# mega-sd-easyeda.net
KiCad netlist of a schematic drawn in EasyEDA Pro
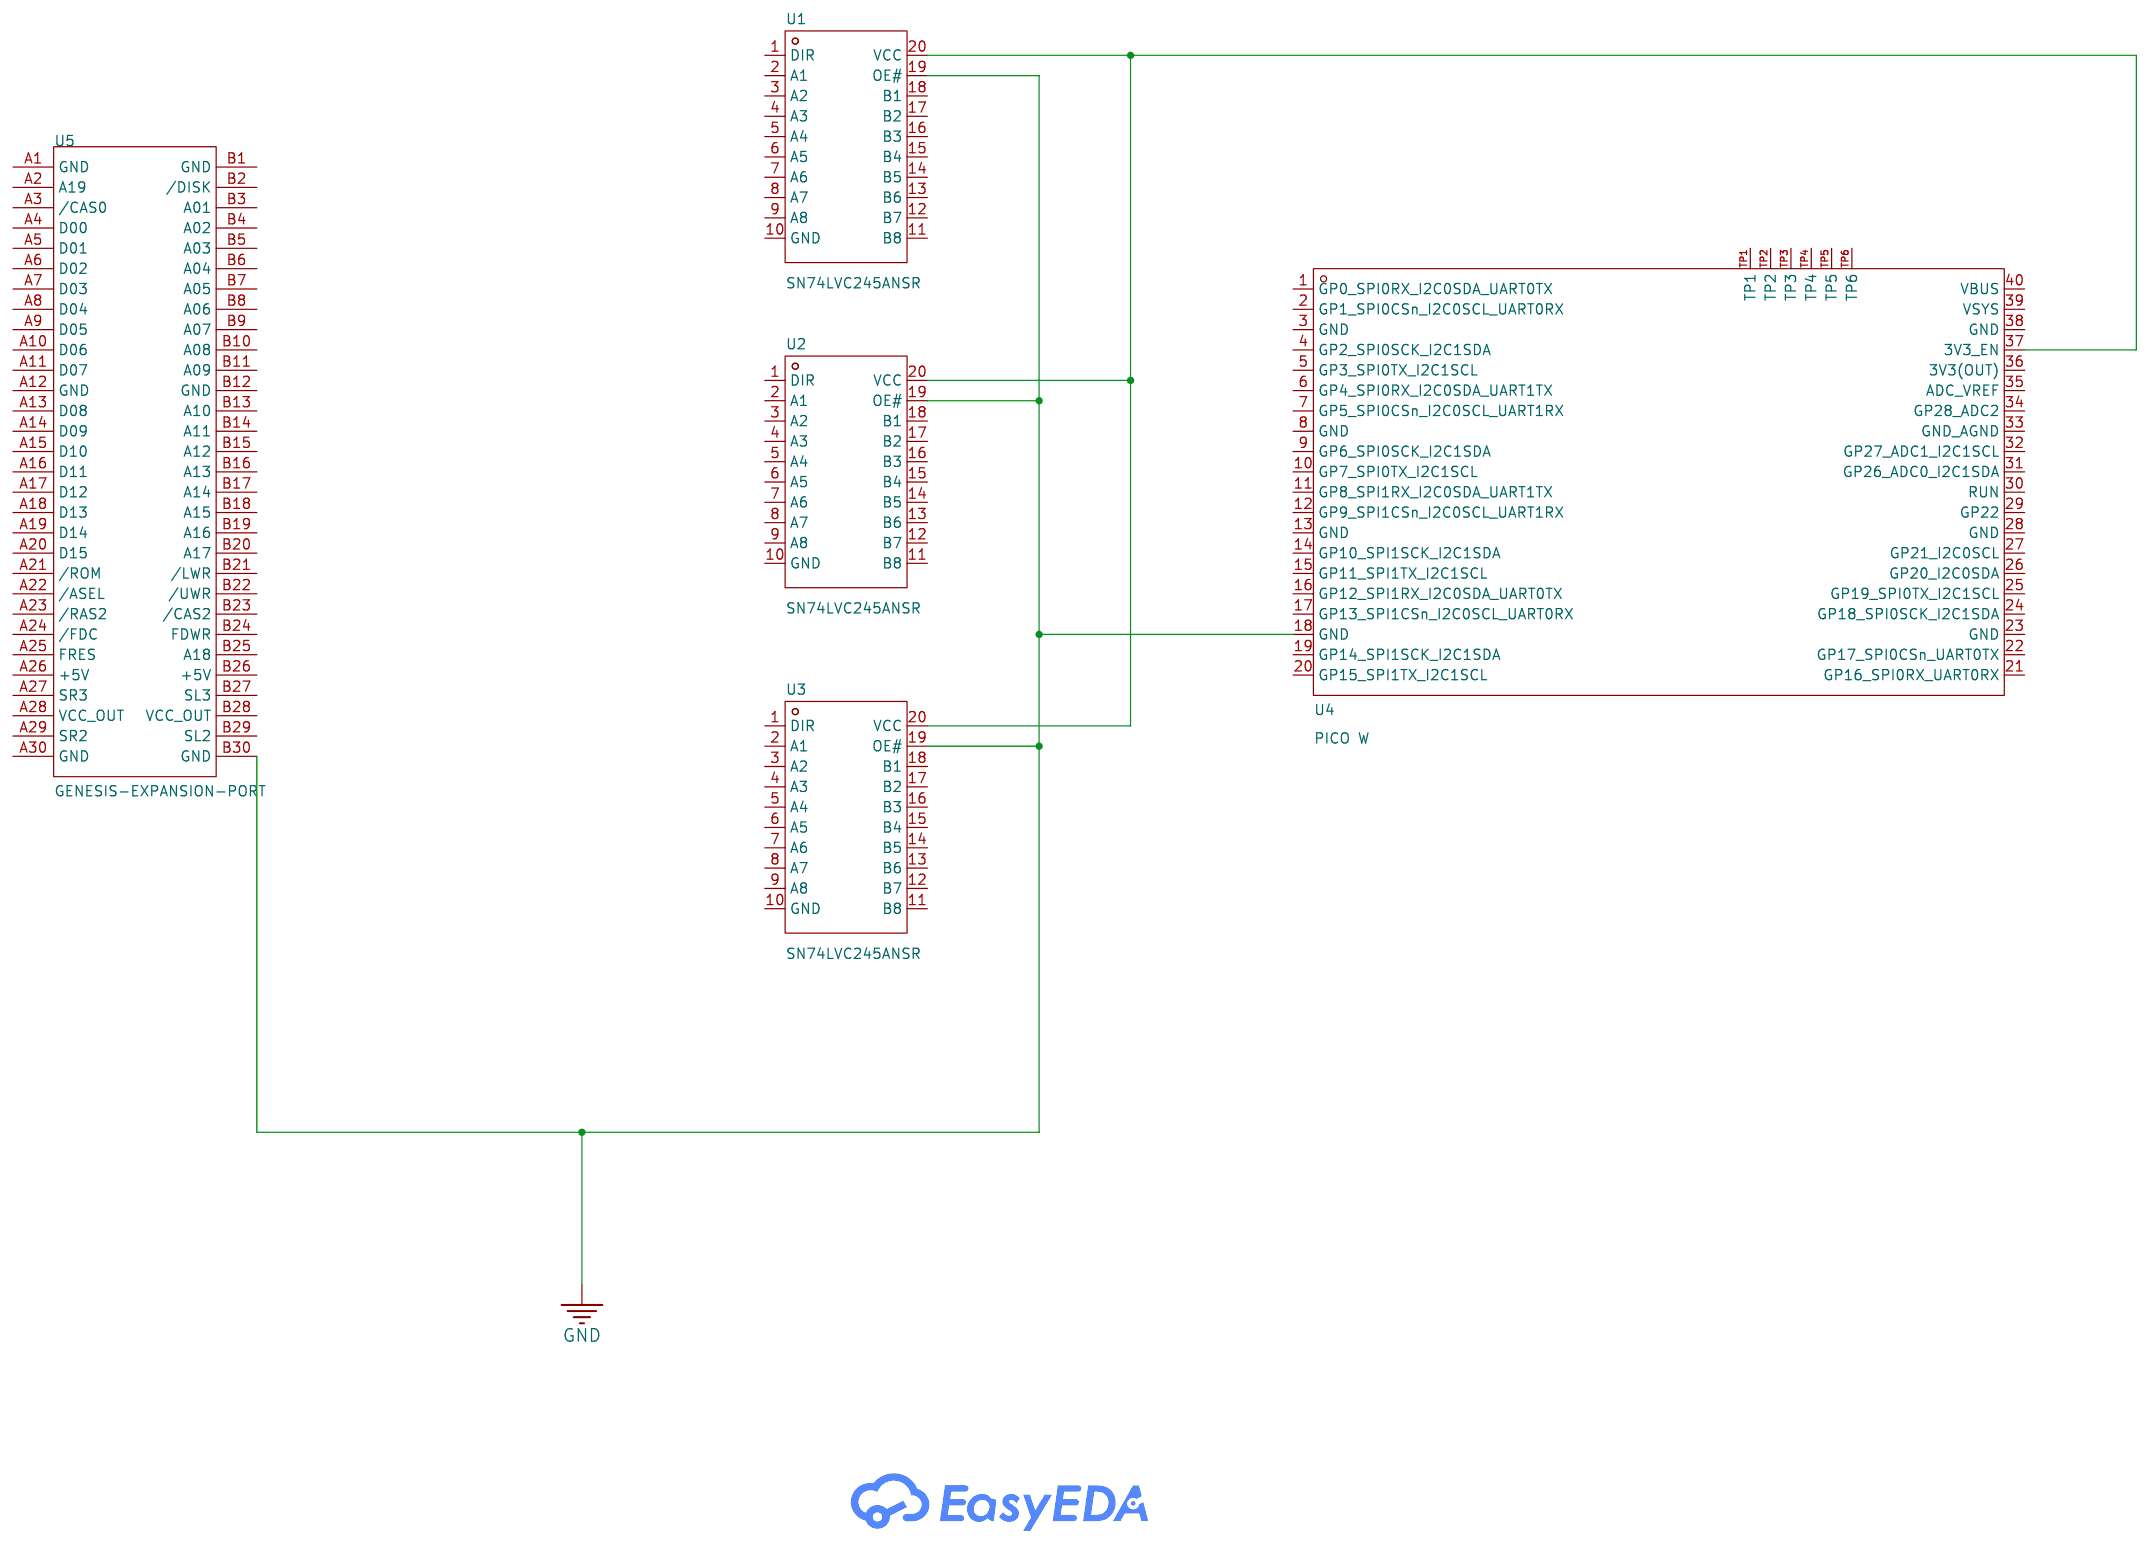
[diagram p0: schematic sheet]

(export (version "E")
  (design (tool "Eeschema 10.0.6"))
  (components
    (comp (ref "U1")
      (value "SN74LVC245ANSR")
      (footprint "easyedapro:SOIC-20_L13.3-W5.5-P1.27-LS7.8-BL")
      (fields (field (name "Manufacturer") "TI(德州仪器)"))
      (libsource (lib "easyedapro") (part "SN74LVC245ANSR"))
    )
    (comp (ref "U2")
      (value "SN74LVC245ANSR")
      (footprint "easyedapro:SOIC-20_L13.3-W5.5-P1.27-LS7.8-BL")
      (fields (field (name "Manufacturer") "TI(德州仪器)"))
      (libsource (lib "easyedapro") (part "SN74LVC245ANSR"))
    )
    (comp (ref "U3")
      (value "SN74LVC245ANSR")
      (footprint "easyedapro:SOIC-20_L13.3-W5.5-P1.27-LS7.8-BL")
      (fields (field (name "Manufacturer") "TI(德州仪器)"))
      (libsource (lib "easyedapro") (part "SN74LVC245ANSR"))
    )
    (comp (ref "U4")
      (value "PICO W")
      (footprint "easyedapro:COMM-SMD_L51.0-W21.0-P2.54_PICOW")
      (fields (field (name "Manufacturer") "Raspberry Pi(树莓派)"))
      (libsource (lib "easyedapro") (part "PICO W"))
    )
    (comp (ref "U5")
      (value "GENESIS-EXPANSION-PORT")
      (footprint "easyedapro:GENESIS-EXPANSION-PORT")
      (libsource (lib "easyedapro") (part "GENESIS-EXPANSION-PORT"))
    )
  )
  (nets
    (net (code "1") (name "GND") (class "Default")
      (node (ref "U1") (pin "19") (pinfunction "OE#_19") (pintype "unspecified"))
      (node (ref "U2") (pin "19") (pinfunction "OE#_19") (pintype "unspecified"))
      (node (ref "U3") (pin "19") (pinfunction "OE#_19") (pintype "unspecified"))
      (node (ref "U4") (pin "18") (pinfunction "GND_18") (pintype "unspecified"))
      (node (ref "U5") (pin "B30") (pinfunction "GND_B30") (pintype "unspecified"))
    )
    (net (code "2") (name "Net-(U1-VCC)") (class "Default")
      (node (ref "U1") (pin "20") (pinfunction "VCC_20") (pintype "unspecified"))
      (node (ref "U2") (pin "20") (pinfunction "VCC_20") (pintype "unspecified"))
      (node (ref "U3") (pin "20") (pinfunction "VCC_20") (pintype "unspecified"))
      (node (ref "U4") (pin "37") (pinfunction "3V3_EN_37") (pintype "unspecified"))
    )
    (net (code "3") (name "unconnected-(U1-A1-Pad2)") (class "Default")
      (node (ref "U1") (pin "2") (pinfunction "A1_2") (pintype "unspecified"))
    )
    (net (code "4") (name "unconnected-(U1-A2-Pad3)") (class "Default")
      (node (ref "U1") (pin "3") (pinfunction "A2_3") (pintype "unspecified"))
    )
    (net (code "5") (name "unconnected-(U1-A3-Pad4)") (class "Default")
      (node (ref "U1") (pin "4") (pinfunction "A3_4") (pintype "unspecified"))
    )
    (net (code "6") (name "unconnected-(U1-A4-Pad5)") (class "Default")
      (node (ref "U1") (pin "5") (pinfunction "A4_5") (pintype "unspecified"))
    )
    (net (code "7") (name "unconnected-(U1-A5-Pad6)") (class "Default")
      (node (ref "U1") (pin "6") (pinfunction "A5_6") (pintype "unspecified"))
    )
    (net (code "8") (name "unconnected-(U1-A6-Pad7)") (class "Default")
      (node (ref "U1") (pin "7") (pinfunction "A6_7") (pintype "unspecified"))
    )
    (net (code "9") (name "unconnected-(U1-A7-Pad8)") (class "Default")
      (node (ref "U1") (pin "8") (pinfunction "A7_8") (pintype "unspecified"))
    )
    (net (code "10") (name "unconnected-(U1-A8-Pad9)") (class "Default")
      (node (ref "U1") (pin "9") (pinfunction "A8_9") (pintype "unspecified"))
    )
    (net (code "11") (name "unconnected-(U1-B1-Pad18)") (class "Default")
      (node (ref "U1") (pin "18") (pinfunction "B1_18") (pintype "unspecified"))
    )
    (net (code "12") (name "unconnected-(U1-B2-Pad17)") (class "Default")
      (node (ref "U1") (pin "17") (pinfunction "B2_17") (pintype "unspecified"))
    )
    (net (code "13") (name "unconnected-(U1-B3-Pad16)") (class "Default")
      (node (ref "U1") (pin "16") (pinfunction "B3_16") (pintype "unspecified"))
    )
    (net (code "14") (name "unconnected-(U1-B4-Pad15)") (class "Default")
      (node (ref "U1") (pin "15") (pinfunction "B4_15") (pintype "unspecified"))
    )
    (net (code "15") (name "unconnected-(U1-B5-Pad14)") (class "Default")
      (node (ref "U1") (pin "14") (pinfunction "B5_14") (pintype "unspecified"))
    )
    (net (code "16") (name "unconnected-(U1-B6-Pad13)") (class "Default")
      (node (ref "U1") (pin "13") (pinfunction "B6_13") (pintype "unspecified"))
    )
    (net (code "17") (name "unconnected-(U1-B7-Pad12)") (class "Default")
      (node (ref "U1") (pin "12") (pinfunction "B7_12") (pintype "unspecified"))
    )
    (net (code "18") (name "unconnected-(U1-B8-Pad11)") (class "Default")
      (node (ref "U1") (pin "11") (pinfunction "B8_11") (pintype "unspecified"))
    )
    (net (code "19") (name "unconnected-(U1-DIR-Pad1)") (class "Default")
      (node (ref "U1") (pin "1") (pinfunction "DIR_1") (pintype "unspecified"))
    )
    (net (code "20") (name "unconnected-(U1-GND-Pad10)") (class "Default")
      (node (ref "U1") (pin "10") (pinfunction "GND_10") (pintype "unspecified"))
    )
    (net (code "21") (name "unconnected-(U2-A1-Pad2)") (class "Default")
      (node (ref "U2") (pin "2") (pinfunction "A1_2") (pintype "unspecified"))
    )
    (net (code "22") (name "unconnected-(U2-A2-Pad3)") (class "Default")
      (node (ref "U2") (pin "3") (pinfunction "A2_3") (pintype "unspecified"))
    )
    (net (code "23") (name "unconnected-(U2-A3-Pad4)") (class "Default")
      (node (ref "U2") (pin "4") (pinfunction "A3_4") (pintype "unspecified"))
    )
    (net (code "24") (name "unconnected-(U2-A4-Pad5)") (class "Default")
      (node (ref "U2") (pin "5") (pinfunction "A4_5") (pintype "unspecified"))
    )
    (net (code "25") (name "unconnected-(U2-A5-Pad6)") (class "Default")
      (node (ref "U2") (pin "6") (pinfunction "A5_6") (pintype "unspecified"))
    )
    (net (code "26") (name "unconnected-(U2-A6-Pad7)") (class "Default")
      (node (ref "U2") (pin "7") (pinfunction "A6_7") (pintype "unspecified"))
    )
    (net (code "27") (name "unconnected-(U2-A7-Pad8)") (class "Default")
      (node (ref "U2") (pin "8") (pinfunction "A7_8") (pintype "unspecified"))
    )
    (net (code "28") (name "unconnected-(U2-A8-Pad9)") (class "Default")
      (node (ref "U2") (pin "9") (pinfunction "A8_9") (pintype "unspecified"))
    )
    (net (code "29") (name "unconnected-(U2-B1-Pad18)") (class "Default")
      (node (ref "U2") (pin "18") (pinfunction "B1_18") (pintype "unspecified"))
    )
    (net (code "30") (name "unconnected-(U2-B2-Pad17)") (class "Default")
      (node (ref "U2") (pin "17") (pinfunction "B2_17") (pintype "unspecified"))
    )
    (net (code "31") (name "unconnected-(U2-B3-Pad16)") (class "Default")
      (node (ref "U2") (pin "16") (pinfunction "B3_16") (pintype "unspecified"))
    )
    (net (code "32") (name "unconnected-(U2-B4-Pad15)") (class "Default")
      (node (ref "U2") (pin "15") (pinfunction "B4_15") (pintype "unspecified"))
    )
    (net (code "33") (name "unconnected-(U2-B5-Pad14)") (class "Default")
      (node (ref "U2") (pin "14") (pinfunction "B5_14") (pintype "unspecified"))
    )
    (net (code "34") (name "unconnected-(U2-B6-Pad13)") (class "Default")
      (node (ref "U2") (pin "13") (pinfunction "B6_13") (pintype "unspecified"))
    )
    (net (code "35") (name "unconnected-(U2-B7-Pad12)") (class "Default")
      (node (ref "U2") (pin "12") (pinfunction "B7_12") (pintype "unspecified"))
    )
    (net (code "36") (name "unconnected-(U2-B8-Pad11)") (class "Default")
      (node (ref "U2") (pin "11") (pinfunction "B8_11") (pintype "unspecified"))
    )
    (net (code "37") (name "unconnected-(U2-DIR-Pad1)") (class "Default")
      (node (ref "U2") (pin "1") (pinfunction "DIR_1") (pintype "unspecified"))
    )
    (net (code "38") (name "unconnected-(U2-GND-Pad10)") (class "Default")
      (node (ref "U2") (pin "10") (pinfunction "GND_10") (pintype "unspecified"))
    )
    (net (code "39") (name "unconnected-(U3-A1-Pad2)") (class "Default")
      (node (ref "U3") (pin "2") (pinfunction "A1_2") (pintype "unspecified"))
    )
    (net (code "40") (name "unconnected-(U3-A2-Pad3)") (class "Default")
      (node (ref "U3") (pin "3") (pinfunction "A2_3") (pintype "unspecified"))
    )
    (net (code "41") (name "unconnected-(U3-A3-Pad4)") (class "Default")
      (node (ref "U3") (pin "4") (pinfunction "A3_4") (pintype "unspecified"))
    )
    (net (code "42") (name "unconnected-(U3-A4-Pad5)") (class "Default")
      (node (ref "U3") (pin "5") (pinfunction "A4_5") (pintype "unspecified"))
    )
    (net (code "43") (name "unconnected-(U3-A5-Pad6)") (class "Default")
      (node (ref "U3") (pin "6") (pinfunction "A5_6") (pintype "unspecified"))
    )
    (net (code "44") (name "unconnected-(U3-A6-Pad7)") (class "Default")
      (node (ref "U3") (pin "7") (pinfunction "A6_7") (pintype "unspecified"))
    )
    (net (code "45") (name "unconnected-(U3-A7-Pad8)") (class "Default")
      (node (ref "U3") (pin "8") (pinfunction "A7_8") (pintype "unspecified"))
    )
    (net (code "46") (name "unconnected-(U3-A8-Pad9)") (class "Default")
      (node (ref "U3") (pin "9") (pinfunction "A8_9") (pintype "unspecified"))
    )
    (net (code "47") (name "unconnected-(U3-B1-Pad18)") (class "Default")
      (node (ref "U3") (pin "18") (pinfunction "B1_18") (pintype "unspecified"))
    )
    (net (code "48") (name "unconnected-(U3-B2-Pad17)") (class "Default")
      (node (ref "U3") (pin "17") (pinfunction "B2_17") (pintype "unspecified"))
    )
    (net (code "49") (name "unconnected-(U3-B3-Pad16)") (class "Default")
      (node (ref "U3") (pin "16") (pinfunction "B3_16") (pintype "unspecified"))
    )
    (net (code "50") (name "unconnected-(U3-B4-Pad15)") (class "Default")
      (node (ref "U3") (pin "15") (pinfunction "B4_15") (pintype "unspecified"))
    )
    (net (code "51") (name "unconnected-(U3-B5-Pad14)") (class "Default")
      (node (ref "U3") (pin "14") (pinfunction "B5_14") (pintype "unspecified"))
    )
    (net (code "52") (name "unconnected-(U3-B6-Pad13)") (class "Default")
      (node (ref "U3") (pin "13") (pinfunction "B6_13") (pintype "unspecified"))
    )
    (net (code "53") (name "unconnected-(U3-B7-Pad12)") (class "Default")
      (node (ref "U3") (pin "12") (pinfunction "B7_12") (pintype "unspecified"))
    )
    (net (code "54") (name "unconnected-(U3-B8-Pad11)") (class "Default")
      (node (ref "U3") (pin "11") (pinfunction "B8_11") (pintype "unspecified"))
    )
    (net (code "55") (name "unconnected-(U3-DIR-Pad1)") (class "Default")
      (node (ref "U3") (pin "1") (pinfunction "DIR_1") (pintype "unspecified"))
    )
    (net (code "56") (name "unconnected-(U3-GND-Pad10)") (class "Default")
      (node (ref "U3") (pin "10") (pinfunction "GND_10") (pintype "unspecified"))
    )
    (net (code "57") (name "unconnected-(U4-3V3(OUT)-Pad36)") (class "Default")
      (node (ref "U4") (pin "36") (pinfunction "3V3(OUT)_36") (pintype "unspecified"))
    )
    (net (code "58") (name "unconnected-(U4-ADC_VREF-Pad35)") (class "Default")
      (node (ref "U4") (pin "35") (pinfunction "ADC_VREF_35") (pintype "unspecified"))
    )
    (net (code "59") (name "unconnected-(U4-GND-Pad3)") (class "Default")
      (node (ref "U4") (pin "3") (pinfunction "GND_3") (pintype "unspecified"))
    )
    (net (code "60") (name "unconnected-(U4-GND-Pad8)") (class "Default")
      (node (ref "U4") (pin "8") (pinfunction "GND_8") (pintype "unspecified"))
    )
    (net (code "61") (name "unconnected-(U4-GND-Pad13)") (class "Default")
      (node (ref "U4") (pin "13") (pinfunction "GND_13") (pintype "unspecified"))
    )
    (net (code "62") (name "unconnected-(U4-GND-Pad23)") (class "Default")
      (node (ref "U4") (pin "23") (pinfunction "GND_23") (pintype "unspecified"))
    )
    (net (code "63") (name "unconnected-(U4-GND-Pad28)") (class "Default")
      (node (ref "U4") (pin "28") (pinfunction "GND_28") (pintype "unspecified"))
    )
    (net (code "64") (name "unconnected-(U4-GND-Pad38)") (class "Default")
      (node (ref "U4") (pin "38") (pinfunction "GND_38") (pintype "unspecified"))
    )
    (net (code "65") (name "unconnected-(U4-GND_AGND-Pad33)") (class "Default")
      (node (ref "U4") (pin "33") (pinfunction "GND_AGND_33") (pintype "unspecified"))
    )
    (net (code "66") (name "unconnected-(U4-GP0_SPI0RX_I2C0SDA_UART0TX-Pad1)") (class "Default")
      (node (ref "U4") (pin "1") (pinfunction "GP0_SPI0RX_I2C0SDA_UART0TX_1") (pintype "unspecified"))
    )
    (net (code "67") (name "unconnected-(U4-GP1_SPI0CSn_I2C0SCL_UART0RX-Pad2)") (class "Default")
      (node (ref "U4") (pin "2") (pinfunction "GP1_SPI0CSn_I2C0SCL_UART0RX_2") (pintype "unspecified"))
    )
    (net (code "68") (name "unconnected-(U4-GP2_SPI0SCK_I2C1SDA-Pad4)") (class "Default")
      (node (ref "U4") (pin "4") (pinfunction "GP2_SPI0SCK_I2C1SDA_4") (pintype "unspecified"))
    )
    (net (code "69") (name "unconnected-(U4-GP3_SPI0TX_I2C1SCL-Pad5)") (class "Default")
      (node (ref "U4") (pin "5") (pinfunction "GP3_SPI0TX_I2C1SCL_5") (pintype "unspecified"))
    )
    (net (code "70") (name "unconnected-(U4-GP4_SPI0RX_I2C0SDA_UART1TX-Pad6)") (class "Default")
      (node (ref "U4") (pin "6") (pinfunction "GP4_SPI0RX_I2C0SDA_UART1TX_6") (pintype "unspecified"))
    )
    (net (code "71") (name "unconnected-(U4-GP5_SPI0CSn_I2C0SCL_UART1RX-Pad7)") (class "Default")
      (node (ref "U4") (pin "7") (pinfunction "GP5_SPI0CSn_I2C0SCL_UART1RX_7") (pintype "unspecified"))
    )
    (net (code "72") (name "unconnected-(U4-GP6_SPI0SCK_I2C1SDA-Pad9)") (class "Default")
      (node (ref "U4") (pin "9") (pinfunction "GP6_SPI0SCK_I2C1SDA_9") (pintype "unspecified"))
    )
    (net (code "73") (name "unconnected-(U4-GP7_SPI0TX_I2C1SCL-Pad10)") (class "Default")
      (node (ref "U4") (pin "10") (pinfunction "GP7_SPI0TX_I2C1SCL_10") (pintype "unspecified"))
    )
    (net (code "74") (name "unconnected-(U4-GP8_SPI1RX_I2C0SDA_UART1TX-Pad11)") (class "Default")
      (node (ref "U4") (pin "11") (pinfunction "GP8_SPI1RX_I2C0SDA_UART1TX_11") (pintype "unspecified"))
    )
    (net (code "75") (name "unconnected-(U4-GP9_SPI1CSn_I2C0SCL_UART1RX-Pad12)") (class "Default")
      (node (ref "U4") (pin "12") (pinfunction "GP9_SPI1CSn_I2C0SCL_UART1RX_12") (pintype "unspecified"))
    )
    (net (code "76") (name "unconnected-(U4-GP10_SPI1SCK_I2C1SDA-Pad14)") (class "Default")
      (node (ref "U4") (pin "14") (pinfunction "GP10_SPI1SCK_I2C1SDA_14") (pintype "unspecified"))
    )
    (net (code "77") (name "unconnected-(U4-GP11_SPI1TX_I2C1SCL-Pad15)") (class "Default")
      (node (ref "U4") (pin "15") (pinfunction "GP11_SPI1TX_I2C1SCL_15") (pintype "unspecified"))
    )
    (net (code "78") (name "unconnected-(U4-GP12_SPI1RX_I2C0SDA_UART0TX-Pad16)") (class "Default")
      (node (ref "U4") (pin "16") (pinfunction "GP12_SPI1RX_I2C0SDA_UART0TX_16") (pintype "unspecified"))
    )
    (net (code "79") (name "unconnected-(U4-GP13_SPI1CSn_I2C0SCL_UART0RX-Pad17)") (class "Default")
      (node (ref "U4") (pin "17") (pinfunction "GP13_SPI1CSn_I2C0SCL_UART0RX_17") (pintype "unspecified"))
    )
    (net (code "80") (name "unconnected-(U4-GP14_SPI1SCK_I2C1SDA-Pad19)") (class "Default")
      (node (ref "U4") (pin "19") (pinfunction "GP14_SPI1SCK_I2C1SDA_19") (pintype "unspecified"))
    )
    (net (code "81") (name "unconnected-(U4-GP15_SPI1TX_I2C1SCL-Pad20)") (class "Default")
      (node (ref "U4") (pin "20") (pinfunction "GP15_SPI1TX_I2C1SCL_20") (pintype "unspecified"))
    )
    (net (code "82") (name "unconnected-(U4-GP16_SPI0RX_UART0RX-Pad21)") (class "Default")
      (node (ref "U4") (pin "21") (pinfunction "GP16_SPI0RX_UART0RX_21") (pintype "unspecified"))
    )
    (net (code "83") (name "unconnected-(U4-GP17_SPI0CSn_UART0TX-Pad22)") (class "Default")
      (node (ref "U4") (pin "22") (pinfunction "GP17_SPI0CSn_UART0TX_22") (pintype "unspecified"))
    )
    (net (code "84") (name "unconnected-(U4-GP18_SPI0SCK_I2C1SDA-Pad24)") (class "Default")
      (node (ref "U4") (pin "24") (pinfunction "GP18_SPI0SCK_I2C1SDA_24") (pintype "unspecified"))
    )
    (net (code "85") (name "unconnected-(U4-GP19_SPI0TX_I2C1SCL-Pad25)") (class "Default")
      (node (ref "U4") (pin "25") (pinfunction "GP19_SPI0TX_I2C1SCL_25") (pintype "unspecified"))
    )
    (net (code "86") (name "unconnected-(U4-GP20_I2C0SDA-Pad26)") (class "Default")
      (node (ref "U4") (pin "26") (pinfunction "GP20_I2C0SDA_26") (pintype "unspecified"))
    )
    (net (code "87") (name "unconnected-(U4-GP21_I2C0SCL-Pad27)") (class "Default")
      (node (ref "U4") (pin "27") (pinfunction "GP21_I2C0SCL_27") (pintype "unspecified"))
    )
    (net (code "88") (name "unconnected-(U4-GP22-Pad29)") (class "Default")
      (node (ref "U4") (pin "29") (pinfunction "GP22_29") (pintype "unspecified"))
    )
    (net (code "89") (name "unconnected-(U4-GP26_ADC0_I2C1SDA-Pad31)") (class "Default")
      (node (ref "U4") (pin "31") (pinfunction "GP26_ADC0_I2C1SDA_31") (pintype "unspecified"))
    )
    (net (code "90") (name "unconnected-(U4-GP27_ADC1_I2C1SCL-Pad32)") (class "Default")
      (node (ref "U4") (pin "32") (pinfunction "GP27_ADC1_I2C1SCL_32") (pintype "unspecified"))
    )
    (net (code "91") (name "unconnected-(U4-GP28_ADC2-Pad34)") (class "Default")
      (node (ref "U4") (pin "34") (pinfunction "GP28_ADC2_34") (pintype "unspecified"))
    )
    (net (code "92") (name "unconnected-(U4-PadTP1)") (class "Default")
      (node (ref "U4") (pin "TP1") (pinfunction "TP1_TP1") (pintype "unspecified"))
    )
    (net (code "93") (name "unconnected-(U4-PadTP2)") (class "Default")
      (node (ref "U4") (pin "TP2") (pinfunction "TP2_TP2") (pintype "unspecified"))
    )
    (net (code "94") (name "unconnected-(U4-PadTP3)") (class "Default")
      (node (ref "U4") (pin "TP3") (pinfunction "TP3_TP3") (pintype "unspecified"))
    )
    (net (code "95") (name "unconnected-(U4-PadTP4)") (class "Default")
      (node (ref "U4") (pin "TP4") (pinfunction "TP4_TP4") (pintype "unspecified"))
    )
    (net (code "96") (name "unconnected-(U4-PadTP5)") (class "Default")
      (node (ref "U4") (pin "TP5") (pinfunction "TP5_TP5") (pintype "unspecified"))
    )
    (net (code "97") (name "unconnected-(U4-PadTP6)") (class "Default")
      (node (ref "U4") (pin "TP6") (pinfunction "TP6_TP6") (pintype "unspecified"))
    )
    (net (code "98") (name "unconnected-(U4-RUN-Pad30)") (class "Default")
      (node (ref "U4") (pin "30") (pinfunction "RUN_30") (pintype "unspecified"))
    )
    (net (code "99") (name "unconnected-(U4-VBUS-Pad40)") (class "Default")
      (node (ref "U4") (pin "40") (pinfunction "VBUS_40") (pintype "unspecified"))
    )
    (net (code "100") (name "unconnected-(U4-VSYS-Pad39)") (class "Default")
      (node (ref "U4") (pin "39") (pinfunction "VSYS_39") (pintype "unspecified"))
    )
    (net (code "101") (name "unconnected-(U5-+5V-PadA26)") (class "Default")
      (node (ref "U5") (pin "A26") (pinfunction "+5V_A26") (pintype "unspecified"))
    )
    (net (code "102") (name "unconnected-(U5-+5V-PadB26)") (class "Default")
      (node (ref "U5") (pin "B26") (pinfunction "+5V_B26") (pintype "unspecified"))
    )
    (net (code "103") (name "unconnected-(U5-A01-PadB3)") (class "Default")
      (node (ref "U5") (pin "B3") (pinfunction "A01_B3") (pintype "unspecified"))
    )
    (net (code "104") (name "unconnected-(U5-A02-PadB4)") (class "Default")
      (node (ref "U5") (pin "B4") (pinfunction "A02_B4") (pintype "unspecified"))
    )
    (net (code "105") (name "unconnected-(U5-A03-PadB5)") (class "Default")
      (node (ref "U5") (pin "B5") (pinfunction "A03_B5") (pintype "unspecified"))
    )
    (net (code "106") (name "unconnected-(U5-A04-PadB6)") (class "Default")
      (node (ref "U5") (pin "B6") (pinfunction "A04_B6") (pintype "unspecified"))
    )
    (net (code "107") (name "unconnected-(U5-A05-PadB7)") (class "Default")
      (node (ref "U5") (pin "B7") (pinfunction "A05_B7") (pintype "unspecified"))
    )
    (net (code "108") (name "unconnected-(U5-A06-PadB8)") (class "Default")
      (node (ref "U5") (pin "B8") (pinfunction "A06_B8") (pintype "unspecified"))
    )
    (net (code "109") (name "unconnected-(U5-A07-PadB9)") (class "Default")
      (node (ref "U5") (pin "B9") (pinfunction "A07_B9") (pintype "unspecified"))
    )
    (net (code "110") (name "unconnected-(U5-A08-PadB10)") (class "Default")
      (node (ref "U5") (pin "B10") (pinfunction "A08_B10") (pintype "unspecified"))
    )
    (net (code "111") (name "unconnected-(U5-A09-PadB11)") (class "Default")
      (node (ref "U5") (pin "B11") (pinfunction "A09_B11") (pintype "unspecified"))
    )
    (net (code "112") (name "unconnected-(U5-A10-PadB13)") (class "Default")
      (node (ref "U5") (pin "B13") (pinfunction "A10_B13") (pintype "unspecified"))
    )
    (net (code "113") (name "unconnected-(U5-A11-PadB14)") (class "Default")
      (node (ref "U5") (pin "B14") (pinfunction "A11_B14") (pintype "unspecified"))
    )
    (net (code "114") (name "unconnected-(U5-A12-PadB15)") (class "Default")
      (node (ref "U5") (pin "B15") (pinfunction "A12_B15") (pintype "unspecified"))
    )
    (net (code "115") (name "unconnected-(U5-A13-PadB16)") (class "Default")
      (node (ref "U5") (pin "B16") (pinfunction "A13_B16") (pintype "unspecified"))
    )
    (net (code "116") (name "unconnected-(U5-A14-PadB17)") (class "Default")
      (node (ref "U5") (pin "B17") (pinfunction "A14_B17") (pintype "unspecified"))
    )
    (net (code "117") (name "unconnected-(U5-A15-PadB18)") (class "Default")
      (node (ref "U5") (pin "B18") (pinfunction "A15_B18") (pintype "unspecified"))
    )
    (net (code "118") (name "unconnected-(U5-A16-PadB19)") (class "Default")
      (node (ref "U5") (pin "B19") (pinfunction "A16_B19") (pintype "unspecified"))
    )
    (net (code "119") (name "unconnected-(U5-A17-PadB20)") (class "Default")
      (node (ref "U5") (pin "B20") (pinfunction "A17_B20") (pintype "unspecified"))
    )
    (net (code "120") (name "unconnected-(U5-A18-PadB25)") (class "Default")
      (node (ref "U5") (pin "B25") (pinfunction "A18_B25") (pintype "unspecified"))
    )
    (net (code "121") (name "unconnected-(U5-A19-PadA2)") (class "Default")
      (node (ref "U5") (pin "A2") (pinfunction "A19_A2") (pintype "unspecified"))
    )
    (net (code "122") (name "unconnected-(U5-D00-PadA4)") (class "Default")
      (node (ref "U5") (pin "A4") (pinfunction "D00_A4") (pintype "unspecified"))
    )
    (net (code "123") (name "unconnected-(U5-D01-PadA5)") (class "Default")
      (node (ref "U5") (pin "A5") (pinfunction "D01_A5") (pintype "unspecified"))
    )
    (net (code "124") (name "unconnected-(U5-D02-PadA6)") (class "Default")
      (node (ref "U5") (pin "A6") (pinfunction "D02_A6") (pintype "unspecified"))
    )
    (net (code "125") (name "unconnected-(U5-D03-PadA7)") (class "Default")
      (node (ref "U5") (pin "A7") (pinfunction "D03_A7") (pintype "unspecified"))
    )
    (net (code "126") (name "unconnected-(U5-D04-PadA8)") (class "Default")
      (node (ref "U5") (pin "A8") (pinfunction "D04_A8") (pintype "unspecified"))
    )
    (net (code "127") (name "unconnected-(U5-D05-PadA9)") (class "Default")
      (node (ref "U5") (pin "A9") (pinfunction "D05_A9") (pintype "unspecified"))
    )
    (net (code "128") (name "unconnected-(U5-D06-PadA10)") (class "Default")
      (node (ref "U5") (pin "A10") (pinfunction "D06_A10") (pintype "unspecified"))
    )
    (net (code "129") (name "unconnected-(U5-D07-PadA11)") (class "Default")
      (node (ref "U5") (pin "A11") (pinfunction "D07_A11") (pintype "unspecified"))
    )
    (net (code "130") (name "unconnected-(U5-D08-PadA13)") (class "Default")
      (node (ref "U5") (pin "A13") (pinfunction "D08_A13") (pintype "unspecified"))
    )
    (net (code "131") (name "unconnected-(U5-D09-PadA14)") (class "Default")
      (node (ref "U5") (pin "A14") (pinfunction "D09_A14") (pintype "unspecified"))
    )
    (net (code "132") (name "unconnected-(U5-D10-PadA15)") (class "Default")
      (node (ref "U5") (pin "A15") (pinfunction "D10_A15") (pintype "unspecified"))
    )
    (net (code "133") (name "unconnected-(U5-D11-PadA16)") (class "Default")
      (node (ref "U5") (pin "A16") (pinfunction "D11_A16") (pintype "unspecified"))
    )
    (net (code "134") (name "unconnected-(U5-D12-PadA17)") (class "Default")
      (node (ref "U5") (pin "A17") (pinfunction "D12_A17") (pintype "unspecified"))
    )
    (net (code "135") (name "unconnected-(U5-D13-PadA18)") (class "Default")
      (node (ref "U5") (pin "A18") (pinfunction "D13_A18") (pintype "unspecified"))
    )
    (net (code "136") (name "unconnected-(U5-D14-PadA19)") (class "Default")
      (node (ref "U5") (pin "A19") (pinfunction "D14_A19") (pintype "unspecified"))
    )
    (net (code "137") (name "unconnected-(U5-D15-PadA20)") (class "Default")
      (node (ref "U5") (pin "A20") (pinfunction "D15_A20") (pintype "unspecified"))
    )
    (net (code "138") (name "unconnected-(U5-FDWR-PadB24)") (class "Default")
      (node (ref "U5") (pin "B24") (pinfunction "FDWR_B24") (pintype "unspecified"))
    )
    (net (code "139") (name "unconnected-(U5-FRES-PadA25)") (class "Default")
      (node (ref "U5") (pin "A25") (pinfunction "FRES_A25") (pintype "unspecified"))
    )
    (net (code "140") (name "unconnected-(U5-GND-PadA1)") (class "Default")
      (node (ref "U5") (pin "A1") (pinfunction "GND_A1") (pintype "unspecified"))
    )
    (net (code "141") (name "unconnected-(U5-GND-PadA12)") (class "Default")
      (node (ref "U5") (pin "A12") (pinfunction "GND_A12") (pintype "unspecified"))
    )
    (net (code "142") (name "unconnected-(U5-GND-PadA30)") (class "Default")
      (node (ref "U5") (pin "A30") (pinfunction "GND_A30") (pintype "unspecified"))
    )
    (net (code "143") (name "unconnected-(U5-GND-PadB1)") (class "Default")
      (node (ref "U5") (pin "B1") (pinfunction "GND_B1") (pintype "unspecified"))
    )
    (net (code "144") (name "unconnected-(U5-GND-PadB12)") (class "Default")
      (node (ref "U5") (pin "B12") (pinfunction "GND_B12") (pintype "unspecified"))
    )
    (net (code "145") (name "unconnected-(U5-SL2-PadB29)") (class "Default")
      (node (ref "U5") (pin "B29") (pinfunction "SL2_B29") (pintype "unspecified"))
    )
    (net (code "146") (name "unconnected-(U5-SL3-PadB27)") (class "Default")
      (node (ref "U5") (pin "B27") (pinfunction "SL3_B27") (pintype "unspecified"))
    )
    (net (code "147") (name "unconnected-(U5-SR2-PadA29)") (class "Default")
      (node (ref "U5") (pin "A29") (pinfunction "SR2_A29") (pintype "unspecified"))
    )
    (net (code "148") (name "unconnected-(U5-SR3-PadA27)") (class "Default")
      (node (ref "U5") (pin "A27") (pinfunction "SR3_A27") (pintype "unspecified"))
    )
    (net (code "149") (name "unconnected-(U5-VCC_OUT-PadA28)") (class "Default")
      (node (ref "U5") (pin "A28") (pinfunction "VCC_OUT_A28") (pintype "unspecified"))
    )
    (net (code "150") (name "unconnected-(U5-VCC_OUT-PadB28)") (class "Default")
      (node (ref "U5") (pin "B28") (pinfunction "VCC_OUT_B28") (pintype "unspecified"))
    )
    (net (code "151") (name "unconnected-(U5-{slash}ASEL-PadA22)") (class "Default")
      (node (ref "U5") (pin "A22") (pinfunction "/ASEL_A22") (pintype "unspecified"))
    )
    (net (code "152") (name "unconnected-(U5-{slash}CAS0-PadA3)") (class "Default")
      (node (ref "U5") (pin "A3") (pinfunction "/CAS0_A3") (pintype "unspecified"))
    )
    (net (code "153") (name "unconnected-(U5-{slash}CAS2-PadB23)") (class "Default")
      (node (ref "U5") (pin "B23") (pinfunction "/CAS2_B23") (pintype "unspecified"))
    )
    (net (code "154") (name "unconnected-(U5-{slash}DISK-PadB2)") (class "Default")
      (node (ref "U5") (pin "B2") (pinfunction "/DISK_B2") (pintype "unspecified"))
    )
    (net (code "155") (name "unconnected-(U5-{slash}FDC-PadA24)") (class "Default")
      (node (ref "U5") (pin "A24") (pinfunction "/FDC_A24") (pintype "unspecified"))
    )
    (net (code "156") (name "unconnected-(U5-{slash}LWR-PadB21)") (class "Default")
      (node (ref "U5") (pin "B21") (pinfunction "/LWR_B21") (pintype "unspecified"))
    )
    (net (code "157") (name "unconnected-(U5-{slash}RAS2-PadA23)") (class "Default")
      (node (ref "U5") (pin "A23") (pinfunction "/RAS2_A23") (pintype "unspecified"))
    )
    (net (code "158") (name "unconnected-(U5-{slash}ROM-PadA21)") (class "Default")
      (node (ref "U5") (pin "A21") (pinfunction "/ROM_A21") (pintype "unspecified"))
    )
    (net (code "159") (name "unconnected-(U5-{slash}UWR-PadB22)") (class "Default")
      (node (ref "U5") (pin "B22") (pinfunction "/UWR_B22") (pintype "unspecified"))
    )
  )
)
